# SD_Card.net
KiCad netlist of a schematic drawn in Altium Designer
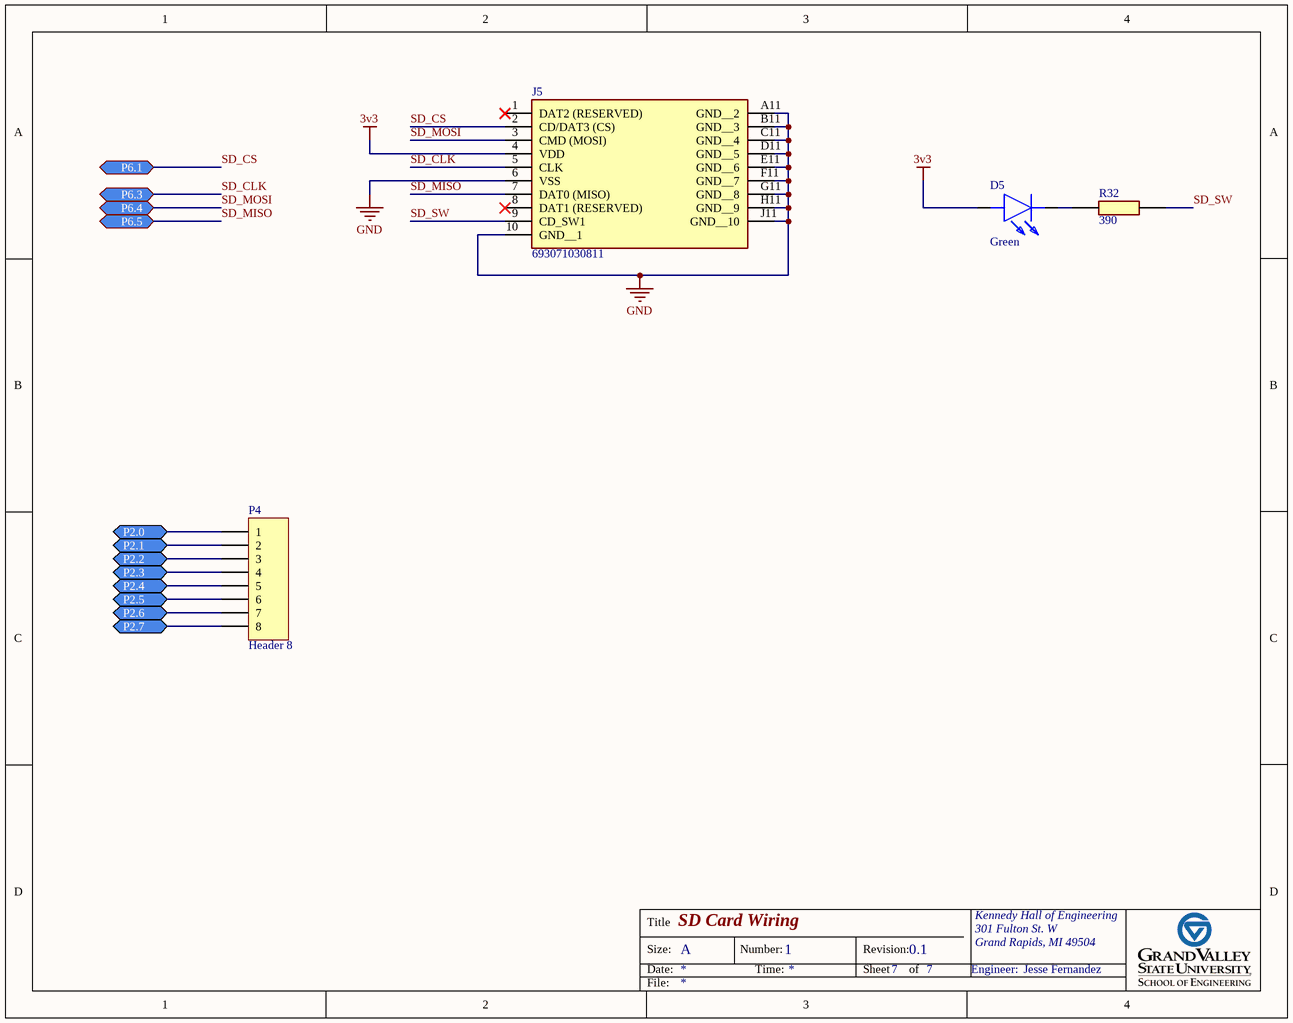
[diagram p0: SD Card.schDoc]

(export (version "E")
  (design (tool "Eeschema 10.0.6"))
  (components
    (comp (ref "D5")
      (value "SML-LX0201UPGC-TR")
      (footprint "SML-LX0201UPGC-TR")
      (description "Standard LEDs - SMD 0201 SMD LEDs 520nm Green")
      (fields (field (name "MANUFACTURER") "Lumex") (field (name "COLOR") "Green"))
      (libsource (lib "UngBung") (part "SML-LX0201UPGC-TR"))
    )
    (comp (ref "J5")
      (value "693071030811")
      (footprint "693071030811")
      (description "Memory Card Connectors WR-CRD_SMT_MicroSD_Push & Push - SW closes to ground")
      (fields (field (name "MANUFACTURER") "Würth Elektronik"))
      (libsource (lib "UngBung") (part "693071030811"))
    )
    (comp (ref "P4")
      (value "Header 8")
      (footprint "HDR1X8")
      (description "Header, 8-Pin")
      (fields (field (name "PUBLISHER") "Altium Limited"))
      (libsource (lib "Miscellaneous Connectors") (part "Header 8"))
    )
    (comp (ref "R32")
      (value "390")
      (footprint "Thin-Film Resistor 0402 (1005 Metric)")
      (description "Resistor, 0402 Package size")
      (fields (field (name "MANUFACTURER") "Yageo") (field (name "TOLERANCE") "1%"))
      (libsource (lib "UngBung") (part "Resistor 0402 (1005 Metric)"))
    )
  )
  (nets
    (net (code "1") (name "/P2.0") (class "Default")
      (node (ref "P4") (pin "1") (pinfunction "1_1") (pintype "passive"))
    )
    (net (code "2") (name "/P2.1") (class "Default")
      (node (ref "P4") (pin "2") (pinfunction "2_2") (pintype "passive"))
    )
    (net (code "3") (name "/P2.2") (class "Default")
      (node (ref "P4") (pin "3") (pinfunction "3_3") (pintype "passive"))
    )
    (net (code "4") (name "/P2.3") (class "Default")
      (node (ref "P4") (pin "4") (pinfunction "4_4") (pintype "passive"))
    )
    (net (code "5") (name "/P2.4") (class "Default")
      (node (ref "P4") (pin "5") (pinfunction "5_5") (pintype "passive"))
    )
    (net (code "6") (name "/P2.5") (class "Default")
      (node (ref "P4") (pin "6") (pinfunction "6_6") (pintype "passive"))
    )
    (net (code "7") (name "/P2.6") (class "Default")
      (node (ref "P4") (pin "7") (pinfunction "7_7") (pintype "passive"))
    )
    (net (code "8") (name "/P2.7") (class "Default")
      (node (ref "P4") (pin "8") (pinfunction "8_8") (pintype "passive"))
    )
    (net (code "9") (name "/SD_CLK") (class "Default")
      (node (ref "J5") (pin "5") (pinfunction "CLK_5") (pintype "passive"))
    )
    (net (code "10") (name "/SD_CS") (class "Default")
      (node (ref "J5") (pin "2") (pinfunction "CD/DAT3_(CS)_2") (pintype "passive"))
    )
    (net (code "11") (name "/SD_MISO") (class "Default")
      (node (ref "J5") (pin "7") (pinfunction "DAT0_(MISO)_7") (pintype "passive"))
    )
    (net (code "12") (name "/SD_MOSI") (class "Default")
      (node (ref "J5") (pin "3") (pinfunction "CMD_(MOSI)_3") (pintype "passive"))
    )
    (net (code "13") (name "/SD_SW") (class "Default")
      (node (ref "J5") (pin "9") (pinfunction "CD_SW1_9") (pintype "passive"))
      (node (ref "R32") (pin "2") (pinfunction "2_2") (pintype "passive"))
    )
    (net (code "14") (name "3v3") (class "Default")
      (node (ref "D5") (pin "2") (pinfunction "A_2") (pintype "passive"))
      (node (ref "J5") (pin "4") (pinfunction "VDD_4") (pintype "passive"))
    )
    (net (code "15") (name "GND") (class "Default")
      (node (ref "J5") (pin "10") (pinfunction "GND__1_10") (pintype "passive"))
      (node (ref "J5") (pin "6") (pinfunction "VSS_6") (pintype "passive"))
      (node (ref "J5") (pin "A11") (pinfunction "GND__2_A11") (pintype "passive"))
      (node (ref "J5") (pin "B11") (pinfunction "GND__3_B11") (pintype "passive"))
      (node (ref "J5") (pin "C11") (pinfunction "GND__4_C11") (pintype "passive"))
      (node (ref "J5") (pin "D11") (pinfunction "GND__5_D11") (pintype "passive"))
      (node (ref "J5") (pin "E11") (pinfunction "GND__6_E11") (pintype "passive"))
      (node (ref "J5") (pin "F11") (pinfunction "GND__7_F11") (pintype "passive"))
      (node (ref "J5") (pin "G11") (pinfunction "GND__8_G11") (pintype "passive"))
      (node (ref "J5") (pin "H11") (pinfunction "GND__9_H11") (pintype "passive"))
      (node (ref "J5") (pin "J11") (pinfunction "GND__10_J11") (pintype "passive"))
    )
    (net (code "16") (name "Net-(D5-K)") (class "Default")
      (node (ref "D5") (pin "1") (pinfunction "K_1") (pintype "passive"))
      (node (ref "R32") (pin "1") (pinfunction "1_1") (pintype "passive"))
    )
    (net (code "17") (name "unconnected-(J5-DAT1_(RESERVED)-Pad8)") (class "Default")
      (node (ref "J5") (pin "8") (pinfunction "DAT1_(RESERVED)_8") (pintype "passive+no_connect"))
    )
    (net (code "18") (name "unconnected-(J5-DAT2_(RESERVED)-Pad1)") (class "Default")
      (node (ref "J5") (pin "1") (pinfunction "DAT2_(RESERVED)_1") (pintype "passive+no_connect"))
    )
  )
)
